# root.net
KiCad netlist of a schematic drawn in Altium Designer
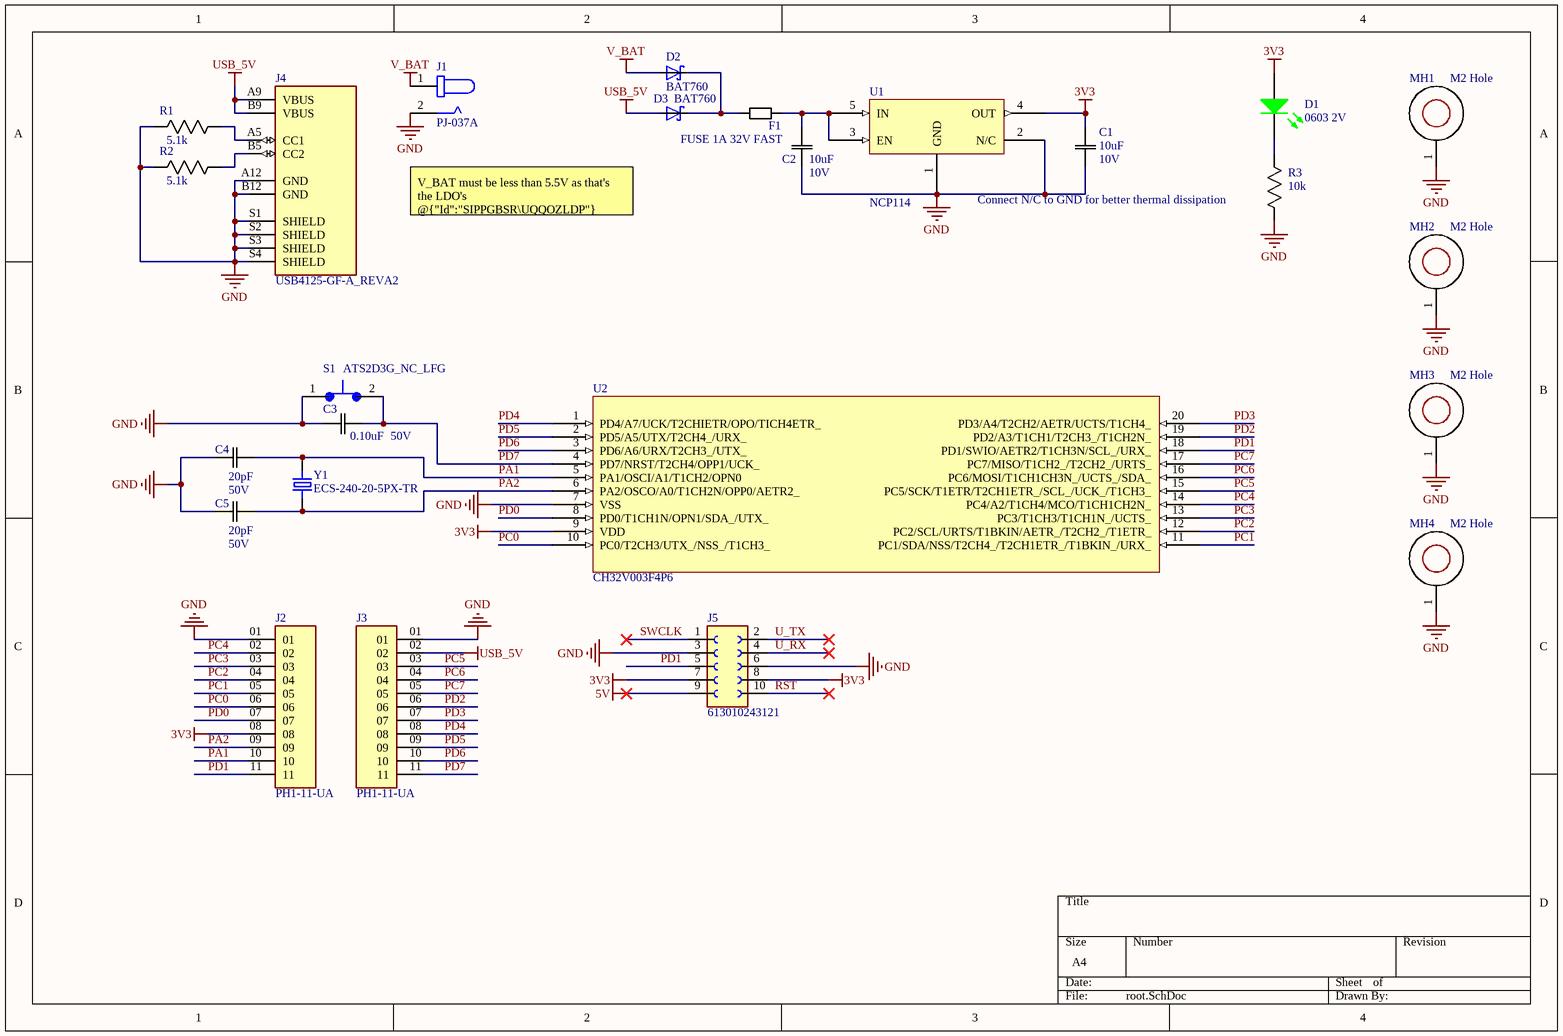
[diagram p0: root.SchDoc]

(export (version "E")
  (design (tool "Eeschema 10.0.6"))
  (components
    (comp (ref "C1")
      (value "10uF")
      (footprint "0603")
      (description "Default Symbol for Capacitors")
      (fields
        (field (name "RATING") "10V")
        (field (name "PART NUMBER") "CAP 10uF 10V")
        (field (name "TOLERANCE") "10%")
      )
      (libsource (lib "capacitor_library") (part "CAP_Default"))
    )
    (comp (ref "C2")
      (value "10uF")
      (footprint "0603")
      (description "Default Symbol for Capacitors")
      (fields
        (field (name "RATING") "10V")
        (field (name "PART NUMBER") "CAP 10uF 10V")
        (field (name "TOLERANCE") "10%")
      )
      (libsource (lib "capacitor_library") (part "CAP_Default"))
    )
    (comp (ref "C3")
      (value "0.10uF")
      (footprint "0603")
      (description "Default Symbol for Capacitors")
      (fields
        (field (name "RATING") "50V")
        (field (name "PART NUMBER") "CAP 0.1uF 50V")
        (field (name "TOLERANCE") "10%")
      )
      (libsource (lib "capacitor_library") (part "CAP_Default"))
    )
    (comp (ref "C4")
      (value "~")
      (footprint "0603")
      (description "CAP CER 22pF 50V C0G 0603/0805")
      (libsource (lib "CAP 20pF 50V") (part "CAP 20pF 50V"))
    )
    (comp (ref "C5")
      (value "~")
      (footprint "0603")
      (description "CAP CER 22pF 50V C0G 0603/0805")
      (libsource (lib "CAP 20pF 50V") (part "CAP 20pF 50V"))
    )
    (comp (ref "D1")
      (value "0603 2V")
      (footprint "0603 - LED")
      (description "LED Uni-Color Green 574nm 2-Pin Chip LED T/R")
      (fields (field (name "PART NUMBER") "LED GREEN SMD 0603"))
      (libsource (lib "Diode_Library") (part "LED GREEN SMD 0603"))
    )
    (comp (ref "D2")
      (value "BAT760")
      (footprint "SOD323(F)")
      (description "Diode Schottky 20V 1A _DC_ Surface Mount SOD-323")
      (fields (field (name "MF") "Nexperia USA"))
      (libsource (lib "BAT760") (part "BAT760"))
    )
    (comp (ref "D3")
      (value "BAT760")
      (footprint "SOD323(F)")
      (description "Diode Schottky 20V 1A _DC_ Surface Mount SOD-323")
      (fields (field (name "MF") "Nexperia USA"))
      (libsource (lib "BAT760") (part "BAT760"))
    )
    (comp (ref "F1")
      (value "FUSE 1A 32V FAST")
      (footprint "0603")
      (description "FUSE 1A 32V DC 0603")
      (libsource (lib "Fuse_Library") (part "FUSE 1A 32V FAST"))
    )
    (comp (ref "J1")
      (value "PJ-037A")
      (footprint "CUI_PJ-037A")
      (description "2.0 mm Center Pin, 2.5 A, Right Angle, Through Hole, Dc Power Jack Connector")
      (libsource (lib "PJ-037A") (part "PJ-037A"))
    )
    (comp (ref "J2")
      (value "PH1-11-UA")
      (footprint "11POS 2.54mm Male Header")
      (description "11POS Male Header")
      (fields (field (name "MP") "TS-111-T-A-1") (field (name "MF") "Samtec"))
      (libsource (lib "TS-111-T-A-1") (part "PH1-11-UA"))
    )
    (comp (ref "J3")
      (value "PH1-11-UA")
      (footprint "11POS 2.54mm Male Header")
      (description "11POS Male Header")
      (fields (field (name "MP") "TS-111-T-A-1") (field (name "MF") "Samtec"))
      (libsource (lib "") (part "PH1-11-UA_1"))
    )
    (comp (ref "J4")
      (value "USB4125-GF-A_REVA2")
      (footprint "GCT_USB4125-GF-A_REVA2")
      (libsource (lib "USB4125-GF-A_REVA2") (part "USB4125-GF-A_REVA2"))
    )
    (comp (ref "J5")
      (value "613010243121")
      (footprint "613010243121")
      (description "10 Position Header Connector Through Hole, Right Angle")
      (fields (field (name "MF") "Wurth Elektronik"))
      (libsource (lib "613010243121") (part "613010243121"))
    )
    (comp (ref "MH1")
      (value "M2 Hole")
      (footprint "Mounting Hole M2")
      (description "Standard M2 Mounting Hole for M2 Standoff")
      (fields (field (name "PART NUMBER") "MOUNTING HOLE M2"))
      (libsource (lib "IC_Library") (part "MOUNTING HOLE M2"))
    )
    (comp (ref "MH2")
      (value "M2 Hole")
      (footprint "Mounting Hole M2")
      (description "Standard M2 Mounting Hole for M2 Standoff")
      (fields (field (name "PART NUMBER") "MOUNTING HOLE M2"))
      (libsource (lib "IC_Library") (part "MOUNTING HOLE M2"))
    )
    (comp (ref "MH3")
      (value "M2 Hole")
      (footprint "Mounting Hole M2")
      (description "Standard M2 Mounting Hole for M2 Standoff")
      (fields (field (name "PART NUMBER") "MOUNTING HOLE M2"))
      (libsource (lib "IC_Library") (part "MOUNTING HOLE M2"))
    )
    (comp (ref "MH4")
      (value "M2 Hole")
      (footprint "Mounting Hole M2")
      (description "Standard M2 Mounting Hole for M2 Standoff")
      (fields (field (name "PART NUMBER") "MOUNTING HOLE M2"))
      (libsource (lib "IC_Library") (part "MOUNTING HOLE M2"))
    )
    (comp (ref "R1")
      (value "5.1k")
      (footprint "0603")
      (description "Default Resistor Symbol")
      (fields (field (name "TOLERANCE") "5%") (field (name "PART NUMBER") "RES 5.1k 1/8W - 1%"))
      (libsource (lib "Resistor_Library") (part "RES_DEFAULT"))
    )
    (comp (ref "R2")
      (value "5.1k")
      (footprint "0603")
      (description "Default Resistor Symbol")
      (fields (field (name "TOLERANCE") "5%") (field (name "PART NUMBER") "RES 5.1k 1/8W - 1%"))
      (libsource (lib "Resistor_Library") (part "RES_DEFAULT"))
    )
    (comp (ref "R3")
      (value "10k")
      (footprint "0603")
      (description "Default Resistor Symbol")
      (fields (field (name "TOLERANCE") "5%") (field (name "PART NUMBER") "RES 10k 1/8W - 1%"))
      (libsource (lib "Resistor_Library") (part "RES_DEFAULT"))
    )
    (comp (ref "S1")
      (value "ATS2D3G_NC_LFG")
      (footprint "SW_ATS2D3G_NC_LFG")
      (description "Tactile Switch SPST-NC Top Actuated Surface Mount")
      (libsource (lib "ATS2D3G_NC_LFG") (part "ATS2D3G_NC_LFG"))
    )
    (comp (ref "U1")
      (value "NCP114")
      (footprint "SOT95P295X110-5NW")
      (libsource (lib "NCP114") (part "NCP114"))
    )
    (comp (ref "U2")
      (value "CH32V003F4P6")
      (footprint "TSOP65P640X110-20N")
      (libsource (lib "CH32V003F4P6") (part "CH32V003F4P6"))
    )
    (comp (ref "Y1")
      (value "ECS-240-20-5PX-TR")
      (footprint "XTAL_ECS-240-20-5PX-TR")
      (description "24 MHz Â±30ppm Crystal 20pF 30 Ohms HC-49/US")
      (fields (field (name "DIGI-KEY_PART_NUMBER") "XC1255TR-ND") (field (name "MF") "ECS Inc."))
      (libsource (lib "ECS-240-20-5PX-TR") (part "ECS-240-20-5PX-TR"))
    )
  )
  (nets
    (net (code "1") (name "/PA1") (class "Default")
      (node (ref "C4") (pin "2") (pinfunction "C2_2") (pintype "passive"))
      (node (ref "J2") (pin "10") (pinfunction "10_10") (pintype "passive"))
      (node (ref "U2") (pin "5") (pinfunction "PA1/OSCI/A1/T1CH2/OPN0_5") (pintype "input"))
      (node (ref "Y1") (pin "1") (pinfunction "1_1") (pintype "passive"))
    )
    (net (code "2") (name "/PA2") (class "Default")
      (node (ref "C5") (pin "2") (pinfunction "C2_2") (pintype "passive"))
      (node (ref "J2") (pin "09") (pinfunction "09_09") (pintype "passive"))
      (node (ref "U2") (pin "6") (pinfunction "PA2/OSCO/A0/T1CH2N/OPP0/AETR2__6") (pintype "input"))
      (node (ref "Y1") (pin "2") (pinfunction "2_2") (pintype "passive"))
    )
    (net (code "3") (name "/PC0") (class "Default")
      (node (ref "J2") (pin "06") (pinfunction "06_06") (pintype "passive"))
      (node (ref "U2") (pin "10") (pinfunction "PC0/T2CH3/UTX_/NSS_/T1CH3__10") (pintype "input"))
    )
    (net (code "4") (name "/PC1") (class "Default")
      (node (ref "J2") (pin "05") (pinfunction "05_05") (pintype "passive"))
      (node (ref "U2") (pin "11") (pinfunction "PC1/SDA/NSS/T2CH4_/T2CH1ETR_/T1BKIN_/URX__11") (pintype "input"))
    )
    (net (code "5") (name "/PC2") (class "Default")
      (node (ref "J2") (pin "04") (pinfunction "04_04") (pintype "passive"))
      (node (ref "U2") (pin "12") (pinfunction "PC2/SCL/URTS/T1BKIN/AETR_/T2CH2_/T1ETR__12") (pintype "input"))
    )
    (net (code "6") (name "/PC3") (class "Default")
      (node (ref "J2") (pin "03") (pinfunction "03_03") (pintype "passive"))
      (node (ref "U2") (pin "13") (pinfunction "PC3/T1CH3/T1CH1N_/UCTS__13") (pintype "input"))
    )
    (net (code "7") (name "/PC4") (class "Default")
      (node (ref "J2") (pin "02") (pinfunction "02_02") (pintype "passive"))
      (node (ref "U2") (pin "14") (pinfunction "PC4/A2/T1CH4/MCO/T1CH1CH2N__14") (pintype "input"))
    )
    (net (code "8") (name "/PC5") (class "Default")
      (node (ref "J3") (pin "03") (pinfunction "03_03") (pintype "passive"))
      (node (ref "U2") (pin "15") (pinfunction "PC5/SCK/T1ETR/T2CH1ETR_/SCL_/UCK_/T1CH3__15") (pintype "input"))
    )
    (net (code "9") (name "/PC6") (class "Default")
      (node (ref "J3") (pin "04") (pinfunction "04_04") (pintype "passive"))
      (node (ref "U2") (pin "16") (pinfunction "PC6/MOSI/T1CH1CH3N_/UCTS_/SDA__16") (pintype "input"))
    )
    (net (code "10") (name "/PC7") (class "Default")
      (node (ref "J3") (pin "05") (pinfunction "05_05") (pintype "passive"))
      (node (ref "U2") (pin "17") (pinfunction "PC7/MISO/T1CH2_/T2CH2_/URTS__17") (pintype "input"))
    )
    (net (code "11") (name "/PD0") (class "Default")
      (node (ref "J2") (pin "07") (pinfunction "07_07") (pintype "passive"))
      (node (ref "U2") (pin "8") (pinfunction "PD0/T1CH1N/OPN1/SDA_/UTX__8") (pintype "input"))
    )
    (net (code "12") (name "/PD1") (class "Default")
      (node (ref "J2") (pin "11") (pinfunction "11_11") (pintype "passive"))
      (node (ref "J5") (pin "5") (pinfunction "3_5") (pintype "passive"))
      (node (ref "U2") (pin "18") (pinfunction "PD1/SWIO/AETR2/T1CH3N/SCL_/URX__18") (pintype "input"))
    )
    (net (code "13") (name "/PD2") (class "Default")
      (node (ref "J3") (pin "06") (pinfunction "06_06") (pintype "passive"))
      (node (ref "U2") (pin "19") (pinfunction "PD2/A3/T1CH1/T2CH3_/T1CH2N__19") (pintype "input"))
    )
    (net (code "14") (name "/PD3") (class "Default")
      (node (ref "J3") (pin "07") (pinfunction "07_07") (pintype "passive"))
      (node (ref "U2") (pin "20") (pinfunction "PD3/A4/T2CH2/AETR/UCTS/T1CH4__20") (pintype "input"))
    )
    (net (code "15") (name "/PD4") (class "Default")
      (node (ref "J3") (pin "08") (pinfunction "08_08") (pintype "passive"))
      (node (ref "U2") (pin "1") (pinfunction "PD4/A7/UCK/T2CHIETR/OPO/TICH4ETR__1") (pintype "input"))
    )
    (net (code "16") (name "/PD5") (class "Default")
      (node (ref "J3") (pin "09") (pinfunction "09_09") (pintype "passive"))
      (node (ref "U2") (pin "2") (pinfunction "PD5/A5/UTX/T2CH4_/URX__2") (pintype "input"))
    )
    (net (code "17") (name "/PD6") (class "Default")
      (node (ref "J3") (pin "10") (pinfunction "10_10") (pintype "passive"))
      (node (ref "U2") (pin "3") (pinfunction "PD6/A6/URX/T2CH3_/UTX__3") (pintype "input"))
    )
    (net (code "18") (name "/PD7") (class "Default")
      (node (ref "C3") (pin "2") (pinfunction "C2_2") (pintype "passive"))
      (node (ref "J3") (pin "11") (pinfunction "11_11") (pintype "passive"))
      (node (ref "S1") (pin "2") (pinfunction "2_2") (pintype "passive"))
      (node (ref "U2") (pin "4") (pinfunction "PD7/NRST/T2CH4/OPP1/UCK__4") (pintype "input"))
    )
    (net (code "19") (name "/RST") (class "Default")
      (node (ref "J5") (pin "10") (pinfunction "6_10") (pintype "passive+no_connect"))
    )
    (net (code "20") (name "/SWCLK") (class "Default")
      (node (ref "J5") (pin "1") (pinfunction "1_1") (pintype "passive+no_connect"))
    )
    (net (code "21") (name "/U_RX") (class "Default")
      (node (ref "J5") (pin "4") (pinfunction "9_4") (pintype "passive+no_connect"))
    )
    (net (code "22") (name "/U_TX") (class "Default")
      (node (ref "J5") (pin "2") (pinfunction "10_2") (pintype "passive+no_connect"))
    )
    (net (code "23") (name "3V3") (class "Default")
      (node (ref "C1") (pin "2") (pinfunction "C2_2") (pintype "passive"))
      (node (ref "D1") (pin "1") (pinfunction "A_1") (pintype "passive"))
      (node (ref "J2") (pin "08") (pinfunction "08_08") (pintype "passive"))
      (node (ref "J5") (pin "7") (pinfunction "4_7") (pintype "passive"))
      (node (ref "J5") (pin "8") (pinfunction "7_8") (pintype "passive"))
      (node (ref "U1") (pin "4") (pinfunction "OUT_4") (pintype "output"))
      (node (ref "U2") (pin "9") (pinfunction "VDD_9") (pintype "input"))
    )
    (net (code "24") (name "5V") (class "Default")
      (node (ref "J5") (pin "9") (pinfunction "5_9") (pintype "passive"))
    )
    (net (code "25") (name "GND") (class "Default")
      (node (ref "C1") (pin "1") (pinfunction "C1_1") (pintype "passive"))
      (node (ref "C2") (pin "1") (pinfunction "C1_1") (pintype "passive"))
      (node (ref "C3") (pin "1") (pinfunction "C1_1") (pintype "passive"))
      (node (ref "C4") (pin "1") (pinfunction "C1_1") (pintype "passive"))
      (node (ref "C5") (pin "1") (pinfunction "C1_1") (pintype "passive"))
      (node (ref "J1") (pin "2") (pinfunction "2_2") (pintype "passive"))
      (node (ref "J2") (pin "01") (pinfunction "01_01") (pintype "passive"))
      (node (ref "J3") (pin "01") (pinfunction "01_01") (pintype "passive"))
      (node (ref "J4") (pin "A12") (pinfunction "GND_A12") (pintype "power_in"))
      (node (ref "J4") (pin "B12") (pinfunction "GND_B12") (pintype "power_in"))
      (node (ref "J4") (pin "S1") (pinfunction "SHIELD_S1") (pintype "passive"))
      (node (ref "J4") (pin "S2") (pinfunction "SHIELD_S2") (pintype "passive"))
      (node (ref "J4") (pin "S3") (pinfunction "SHIELD_S3") (pintype "passive"))
      (node (ref "J4") (pin "S4") (pinfunction "SHIELD_S4") (pintype "passive"))
      (node (ref "J5") (pin "3") (pinfunction "2_3") (pintype "passive"))
      (node (ref "J5") (pin "6") (pinfunction "8_6") (pintype "passive"))
      (node (ref "MH1") (pin "1") (pinfunction "1_1") (pintype "passive"))
      (node (ref "MH2") (pin "1") (pinfunction "1_1") (pintype "passive"))
      (node (ref "MH3") (pin "1") (pinfunction "1_1") (pintype "passive"))
      (node (ref "MH4") (pin "1") (pinfunction "1_1") (pintype "passive"))
      (node (ref "R1") (pin "2") (pinfunction "R2_2") (pintype "passive"))
      (node (ref "R2") (pin "2") (pinfunction "R2_2") (pintype "passive"))
      (node (ref "R3") (pin "1") (pinfunction "R1_1") (pintype "passive"))
      (node (ref "S1") (pin "1") (pinfunction "1_1") (pintype "passive"))
      (node (ref "U1") (pin "1") (pinfunction "GND_1") (pintype "power_in"))
      (node (ref "U1") (pin "2") (pinfunction "N/C_2") (pintype "passive"))
      (node (ref "U2") (pin "7") (pinfunction "VSS_7") (pintype "input"))
    )
    (net (code "26") (name "Net-(C2-C2)") (class "Default")
      (node (ref "C2") (pin "2") (pinfunction "C2_2") (pintype "passive"))
      (node (ref "F1") (pin "2") (pinfunction "2_2") (pintype "passive"))
      (node (ref "U1") (pin "3") (pinfunction "EN_3") (pintype "input"))
      (node (ref "U1") (pin "5") (pinfunction "IN_5") (pintype "input"))
    )
    (net (code "27") (name "Net-(D1-K)") (class "Default")
      (node (ref "D1") (pin "2") (pinfunction "K_2") (pintype "passive"))
      (node (ref "R3") (pin "2") (pinfunction "R2_2") (pintype "passive"))
    )
    (net (code "28") (name "Net-(D2-K)") (class "Default")
      (node (ref "D2") (pin "1") (pinfunction "K_1") (pintype "passive"))
      (node (ref "D3") (pin "1") (pinfunction "K_1") (pintype "passive"))
      (node (ref "F1") (pin "1") (pinfunction "1_1") (pintype "passive"))
    )
    (net (code "29") (name "Net-(J4-CC1)") (class "Default")
      (node (ref "J4") (pin "A5") (pinfunction "CC1_A5") (pintype "bidirectional"))
      (node (ref "R1") (pin "1") (pinfunction "R1_1") (pintype "passive"))
    )
    (net (code "30") (name "Net-(J4-CC2)") (class "Default")
      (node (ref "J4") (pin "B5") (pinfunction "CC2_B5") (pintype "bidirectional"))
      (node (ref "R2") (pin "1") (pinfunction "R1_1") (pintype "passive"))
    )
    (net (code "31") (name "USB_5V") (class "Default")
      (node (ref "D3") (pin "2") (pinfunction "A_2") (pintype "passive"))
      (node (ref "J3") (pin "02") (pinfunction "02_02") (pintype "passive"))
      (node (ref "J4") (pin "A9") (pinfunction "VBUS_A9") (pintype "power_in"))
      (node (ref "J4") (pin "B9") (pinfunction "VBUS_B9") (pintype "power_in"))
    )
    (net (code "32") (name "V_BAT") (class "Default")
      (node (ref "D2") (pin "2") (pinfunction "A_2") (pintype "passive"))
      (node (ref "J1") (pin "1") (pinfunction "1_1") (pintype "passive"))
    )
  )
)
